# BPMLabLineRX3_1.net
KiCad netlist of a schematic drawn in EAGLE
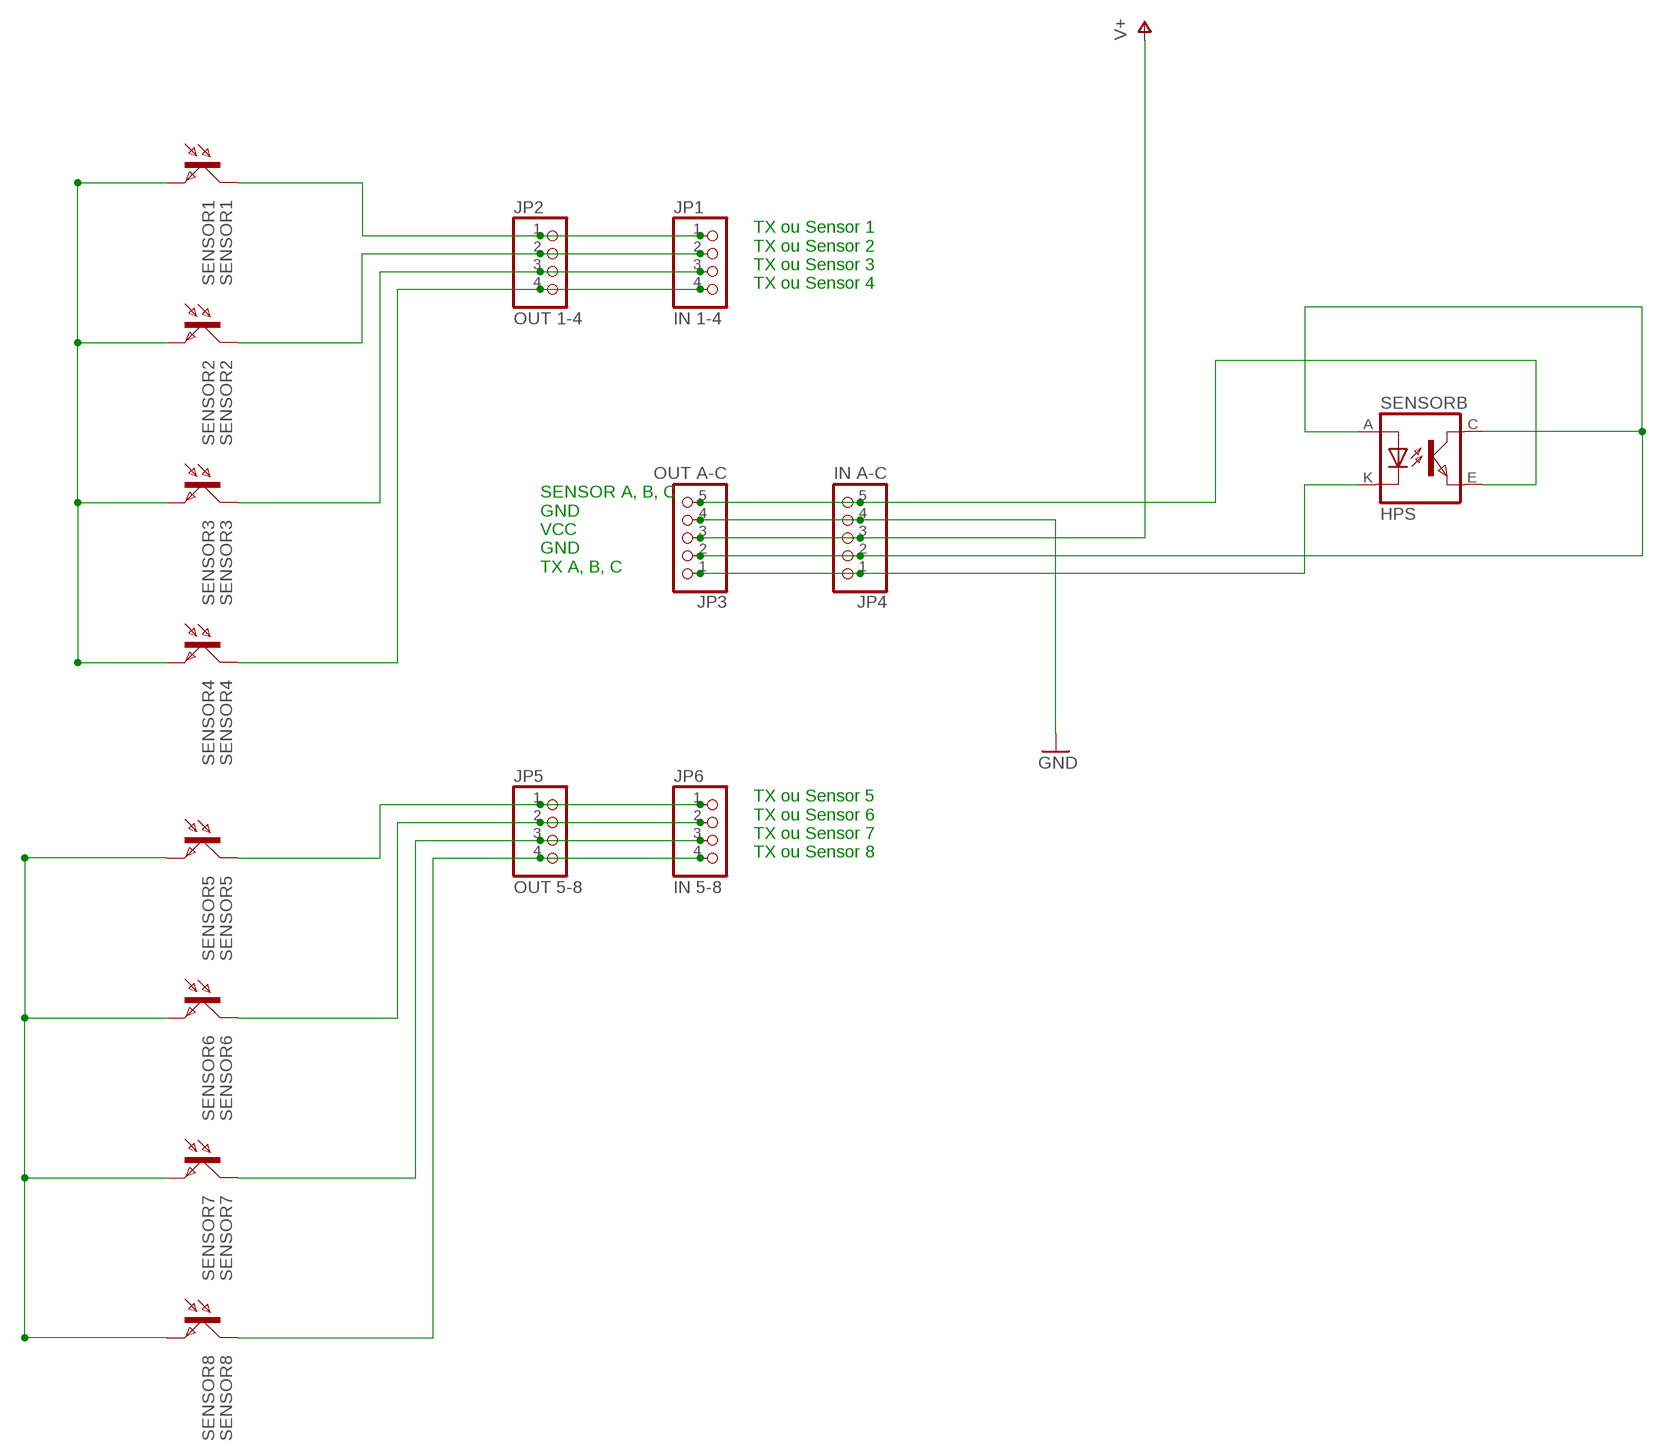
[diagram p0: schematic, sheet 1]

(export (version "E")
  (design (tool "Eeschema 10.0.6"))
  (components
    (comp (ref "JP1")
      (value "IN 1-4")
      (footprint "eagle-import:1X04")
      (libsource (lib "eagle-import") (part "PINHD-1X4"))
    )
    (comp (ref "JP2")
      (value "OUT 1-4")
      (footprint "eagle-import:1X04")
      (libsource (lib "eagle-import") (part "PINHD-1X4"))
    )
    (comp (ref "JP3")
      (value "OUT A-C")
      (footprint "eagle-import:1X05")
      (libsource (lib "eagle-import") (part "PINHD-1X5"))
    )
    (comp (ref "JP4")
      (value "IN A-C")
      (footprint "eagle-import:1X05")
      (libsource (lib "eagle-import") (part "PINHD-1X5"))
    )
    (comp (ref "JP5")
      (value "OUT 5-8")
      (footprint "eagle-import:1X04")
      (libsource (lib "eagle-import") (part "PINHD-1X4"))
    )
    (comp (ref "JP6")
      (value "IN 5-8")
      (footprint "eagle-import:1X04")
      (libsource (lib "eagle-import") (part "PINHD-1X4"))
    )
    (comp (ref "SENSOR1")
      (value "SENSOR1")
      (footprint "eagle-import:BPX81")
      (libsource (lib "eagle-import") (part "BPX81"))
    )
    (comp (ref "SENSOR2")
      (value "SENSOR2")
      (footprint "eagle-import:BPX81")
      (libsource (lib "eagle-import") (part "BPX81"))
    )
    (comp (ref "SENSOR3")
      (value "SENSOR3")
      (footprint "eagle-import:BPX81")
      (libsource (lib "eagle-import") (part "BPX81"))
    )
    (comp (ref "SENSOR4")
      (value "SENSOR4")
      (footprint "eagle-import:BPX81")
      (libsource (lib "eagle-import") (part "BPX81"))
    )
    (comp (ref "SENSOR5")
      (value "SENSOR5")
      (footprint "eagle-import:BPX81")
      (libsource (lib "eagle-import") (part "BPX81"))
    )
    (comp (ref "SENSOR6")
      (value "SENSOR6")
      (footprint "eagle-import:BPX81")
      (libsource (lib "eagle-import") (part "BPX81"))
    )
    (comp (ref "SENSOR7")
      (value "SENSOR7")
      (footprint "eagle-import:BPX81")
      (libsource (lib "eagle-import") (part "BPX81"))
    )
    (comp (ref "SENSOR8")
      (value "SENSOR8")
      (footprint "eagle-import:BPX81")
      (libsource (lib "eagle-import") (part "BPX81"))
    )
    (comp (ref "SENSORB")
      (value "HPS")
      (footprint "eagle-import:TCRT5000")
      (libsource (lib "eagle-import") (part "TCRT5000"))
    )
  )
  (nets
    (net (code "1") (name "GND") (class "Default")
      (node (ref "JP3") (pin "4") (pinfunction "4_4") (pintype "passive"))
      (node (ref "JP4") (pin "4") (pinfunction "4_4") (pintype "passive"))
    )
    (net (code "2") (name "Net-(JP1-Pad1)") (class "Default")
      (node (ref "JP1") (pin "1") (pinfunction "1_1") (pintype "passive"))
      (node (ref "JP2") (pin "1") (pinfunction "1_1") (pintype "passive"))
      (node (ref "SENSOR1") (pin "C") (pinfunction "C_C") (pintype "passive"))
    )
    (net (code "3") (name "Net-(JP1-Pad2)") (class "Default")
      (node (ref "JP1") (pin "2") (pinfunction "2_2") (pintype "passive"))
      (node (ref "JP2") (pin "2") (pinfunction "2_2") (pintype "passive"))
      (node (ref "SENSOR2") (pin "C") (pinfunction "C_C") (pintype "passive"))
    )
    (net (code "4") (name "Net-(JP1-Pad3)") (class "Default")
      (node (ref "JP1") (pin "3") (pinfunction "3_3") (pintype "passive"))
      (node (ref "JP2") (pin "3") (pinfunction "3_3") (pintype "passive"))
      (node (ref "SENSOR3") (pin "C") (pinfunction "C_C") (pintype "passive"))
    )
    (net (code "5") (name "Net-(JP1-Pad4)") (class "Default")
      (node (ref "JP1") (pin "4") (pinfunction "4_4") (pintype "passive"))
      (node (ref "JP2") (pin "4") (pinfunction "4_4") (pintype "passive"))
      (node (ref "SENSOR4") (pin "C") (pinfunction "C_C") (pintype "passive"))
    )
    (net (code "6") (name "Net-(JP5-Pad1)") (class "Default")
      (node (ref "JP5") (pin "1") (pinfunction "1_1") (pintype "passive"))
      (node (ref "JP6") (pin "1") (pinfunction "1_1") (pintype "passive"))
      (node (ref "SENSOR5") (pin "C") (pinfunction "C_C") (pintype "passive"))
    )
    (net (code "7") (name "Net-(JP5-Pad2)") (class "Default")
      (node (ref "JP5") (pin "2") (pinfunction "2_2") (pintype "passive"))
      (node (ref "JP6") (pin "2") (pinfunction "2_2") (pintype "passive"))
      (node (ref "SENSOR6") (pin "C") (pinfunction "C_C") (pintype "passive"))
    )
    (net (code "8") (name "Net-(JP5-Pad3)") (class "Default")
      (node (ref "JP5") (pin "3") (pinfunction "3_3") (pintype "passive"))
      (node (ref "JP6") (pin "3") (pinfunction "3_3") (pintype "passive"))
      (node (ref "SENSOR7") (pin "C") (pinfunction "C_C") (pintype "passive"))
    )
    (net (code "9") (name "Net-(JP5-Pad4)") (class "Default")
      (node (ref "JP5") (pin "4") (pinfunction "4_4") (pintype "passive"))
      (node (ref "JP6") (pin "4") (pinfunction "4_4") (pintype "passive"))
      (node (ref "SENSOR8") (pin "C") (pinfunction "C_C") (pintype "passive"))
    )
    (net (code "10") (name "Net-(SENSOR1-PadE)") (class "Default")
      (node (ref "SENSOR1") (pin "E") (pinfunction "E_E") (pintype "passive"))
      (node (ref "SENSOR2") (pin "E") (pinfunction "E_E") (pintype "passive"))
      (node (ref "SENSOR3") (pin "E") (pinfunction "E_E") (pintype "passive"))
      (node (ref "SENSOR4") (pin "E") (pinfunction "E_E") (pintype "passive"))
    )
    (net (code "11") (name "Net-(SENSOR5-PadE)") (class "Default")
      (node (ref "SENSOR5") (pin "E") (pinfunction "E_E") (pintype "passive"))
      (node (ref "SENSOR6") (pin "E") (pinfunction "E_E") (pintype "passive"))
      (node (ref "SENSOR7") (pin "E") (pinfunction "E_E") (pintype "passive"))
      (node (ref "SENSOR8") (pin "E") (pinfunction "E_E") (pintype "passive"))
    )
    (net (code "12") (name "Net-(SENSORB-ANODE)") (class "Default")
      (node (ref "JP3") (pin "2") (pinfunction "2_2") (pintype "passive"))
      (node (ref "JP4") (pin "2") (pinfunction "2_2") (pintype "passive"))
      (node (ref "SENSORB") (pin "A") (pinfunction "ANODE_A") (pintype "passive"))
      (node (ref "SENSORB") (pin "C") (pinfunction "COLLECTOR_C") (pintype "passive"))
    )
    (net (code "13") (name "Net-(SENSORB-CATHODE)") (class "Default")
      (node (ref "JP3") (pin "1") (pinfunction "1_1") (pintype "passive"))
      (node (ref "JP4") (pin "1") (pinfunction "1_1") (pintype "passive"))
      (node (ref "SENSORB") (pin "K") (pinfunction "CATHODE_K") (pintype "passive"))
    )
    (net (code "14") (name "Net-(SENSORB-EMITTER)") (class "Default")
      (node (ref "JP3") (pin "5") (pinfunction "5_5") (pintype "passive"))
      (node (ref "JP4") (pin "5") (pinfunction "5_5") (pintype "passive"))
      (node (ref "SENSORB") (pin "E") (pinfunction "EMITTER_E") (pintype "passive"))
    )
    (net (code "15") (name "V+") (class "Default")
      (node (ref "JP3") (pin "3") (pinfunction "3_3") (pintype "passive"))
      (node (ref "JP4") (pin "3") (pinfunction "3_3") (pintype "passive"))
    )
  )
)
